# source_eagle.net
KiCad netlist of a schematic drawn in EAGLE
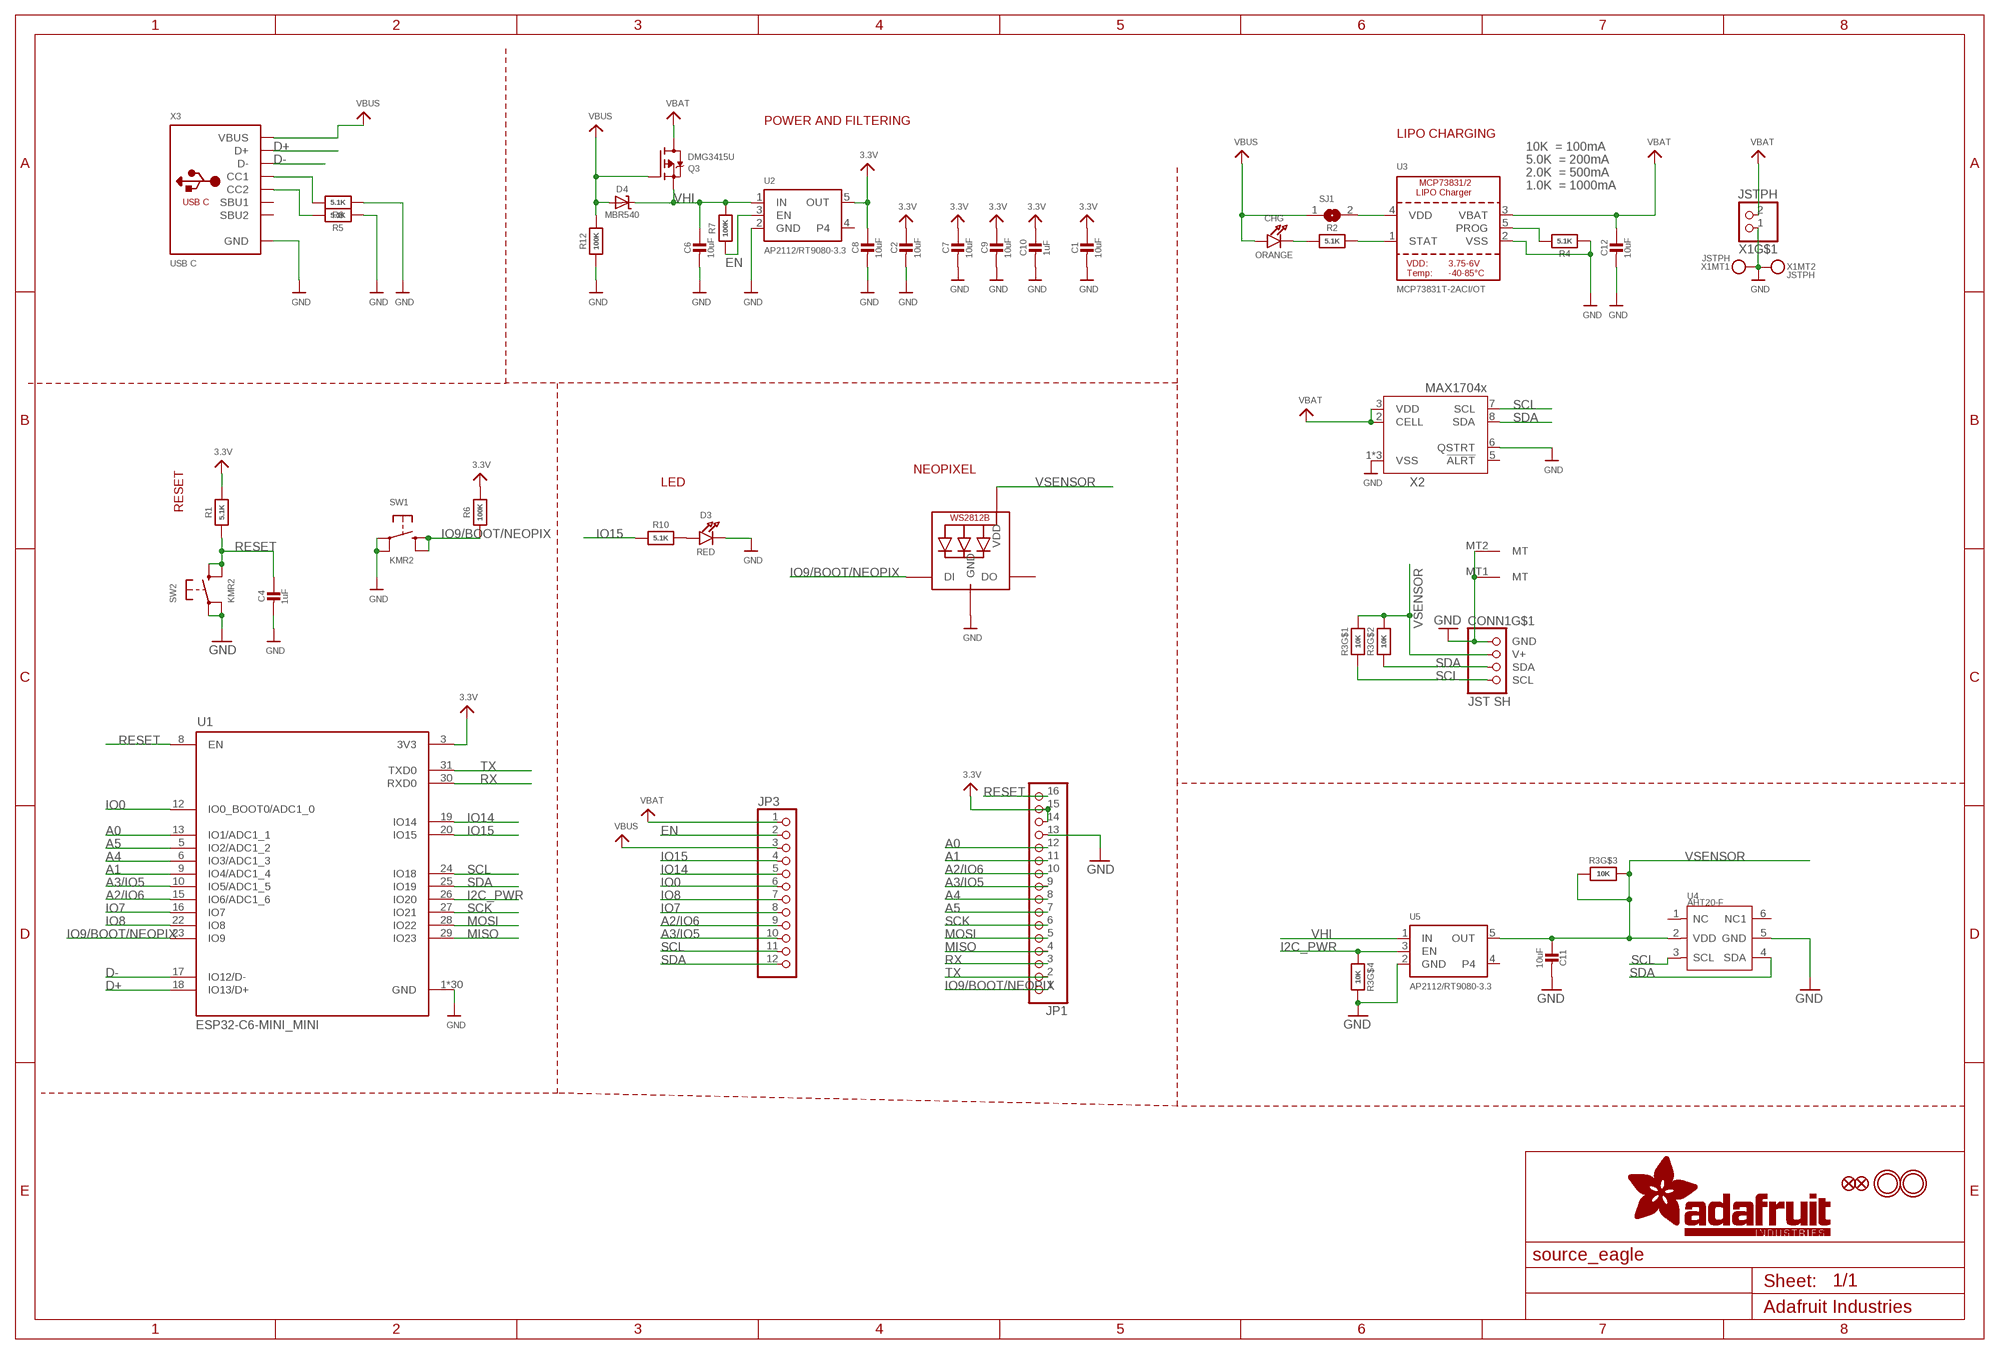
[diagram p0: schematic, sheet 1]

(export (version "E")
  (design (tool "Eeschema 10.0.6"))
  (components
    (comp (ref "C1")
      (value "10uF")
      (footprint "eagle-import:0805-NO")
      (libsource (lib "eagle-import") (part "CAP_CERAMIC0805-NOOUTLINE"))
    )
    (comp (ref "C2")
      (value "10uF")
      (footprint "eagle-import:0805-NO")
      (libsource (lib "eagle-import") (part "CAP_CERAMIC0805-NOOUTLINE"))
    )
    (comp (ref "C4")
      (value "1uF")
      (footprint "eagle-import:0603-NO")
      (libsource (lib "eagle-import") (part "CAP_CERAMIC0603_NO"))
    )
    (comp (ref "C6")
      (value "10uF")
      (footprint "eagle-import:0805-NO")
      (libsource (lib "eagle-import") (part "CAP_CERAMIC0805-NOOUTLINE"))
    )
    (comp (ref "C7")
      (value "10uF")
      (footprint "eagle-import:0805-NO")
      (libsource (lib "eagle-import") (part "CAP_CERAMIC0805-NOOUTLINE"))
    )
    (comp (ref "C8")
      (value "10uF")
      (footprint "eagle-import:0805-NO")
      (fields (field (name "REV") "B"))
      (libsource (lib "eagle-import") (part "CAP_CERAMIC0805-NOOUTLINE"))
    )
    (comp (ref "C9")
      (value "10uF")
      (footprint "eagle-import:0805-NO")
      (libsource (lib "eagle-import") (part "CAP_CERAMIC0805-NOOUTLINE"))
    )
    (comp (ref "C10")
      (value "1uF")
      (footprint "eagle-import:0603-NO")
      (libsource (lib "eagle-import") (part "CAP_CERAMIC0603_NO"))
    )
    (comp (ref "C11")
      (value "10uF")
      (footprint "eagle-import:0805-NO")
      (libsource (lib "eagle-import") (part "CAP_CERAMIC0805-NOOUTLINE"))
    )
    (comp (ref "C12")
      (value "10uF")
      (footprint "eagle-import:_0805MP")
      (libsource (lib "eagle-import") (part "CAP_CERAMIC_0805MP"))
    )
    (comp (ref "CHG")
      (value "ORANGE")
      (footprint "eagle-import:CHIPLED_0603_NOOUTLINE")
      (libsource (lib "eagle-import") (part "LED0603_NOOUTLINE"))
    )
    (comp (ref "CONN1")
      (value "JST SH")
      (footprint "eagle-import:JST_SH4_RA")
      (libsource (lib "eagle-import") (part "STEMMA_I2C_QTRA"))
    )
    (comp (ref "D3")
      (value "RED")
      (footprint "eagle-import:CHIPLED_0603_NOOUTLINE")
      (libsource (lib "eagle-import") (part "LED0603_NOOUTLINE"))
    )
    (comp (ref "D4")
      (value "MBR540")
      (footprint "eagle-import:SOD-123")
      (libsource (lib "eagle-import") (part "DIODE-SCHOTTKYSOD-123"))
    )
    (comp (ref "JP1")
      (value "HEADER-1X16ROUND")
      (footprint "eagle-import:1X16_ROUND")
      (libsource (lib "eagle-import") (part "HEADER-1X16ROUND"))
    )
    (comp (ref "JP3")
      (value "HEADER-1X12")
      (footprint "eagle-import:1X12_ROUND")
      (libsource (lib "eagle-import") (part "HEADER-1X12"))
    )
    (comp (ref "LED1")
      (value "WS2812B_3535FULL")
      (footprint "eagle-import:LED3535_FULLPADS")
      (libsource (lib "eagle-import") (part "WS2812B_3535FULL"))
    )
    (comp (ref "Q3")
      (value "DMG3415U")
      (footprint "eagle-import:SOT23-R")
      (libsource (lib "eagle-import") (part "MOSFET-P"))
    )
    (comp (ref "R1")
      (value "5.1K")
      (footprint "eagle-import:0603-NO")
      (libsource (lib "eagle-import") (part "RESISTOR_0603_NOOUT"))
    )
    (comp (ref "R2")
      (value "5.1K")
      (footprint "eagle-import:0603-NO")
      (libsource (lib "eagle-import") (part "RESISTOR_0603_NOOUT"))
    )
    (comp (ref "R3")
      (value "10K")
      (footprint "eagle-import:RESPACK_4X0603")
      (libsource (lib "eagle-import") (part "RESISTOR_4PACK"))
    )
    (comp (ref "R4")
      (value "5.1K")
      (footprint "eagle-import:0603-NO")
      (libsource (lib "eagle-import") (part "RESISTOR_0603_NOOUT"))
    )
    (comp (ref "R5")
      (value "5.1K")
      (footprint "eagle-import:0603-NO")
      (libsource (lib "eagle-import") (part "RESISTOR_0603_NOOUT"))
    )
    (comp (ref "R6")
      (value "100K")
      (footprint "eagle-import:0603-NO")
      (libsource (lib "eagle-import") (part "RESISTOR_0603_NOOUT"))
    )
    (comp (ref "R7")
      (value "100K")
      (footprint "eagle-import:0603-NO")
      (libsource (lib "eagle-import") (part "RESISTOR_0603_NOOUT"))
    )
    (comp (ref "R8")
      (value "5.1K")
      (footprint "eagle-import:0603-NO")
      (libsource (lib "eagle-import") (part "RESISTOR_0603_NOOUT"))
    )
    (comp (ref "R10")
      (value "5.1K")
      (footprint "eagle-import:0603-NO")
      (libsource (lib "eagle-import") (part "RESISTOR_0603_NOOUT"))
    )
    (comp (ref "R12")
      (value "100K")
      (footprint "eagle-import:0603-NO")
      (libsource (lib "eagle-import") (part "RESISTOR_0603_NOOUT"))
    )
    (comp (ref "SJ1")
      (value "SOLDERJUMPERCLOSED")
      (footprint "eagle-import:SOLDERJUMPER_CLOSEDWIRE")
      (libsource (lib "eagle-import") (part "SOLDERJUMPERCLOSED"))
    )
    (comp (ref "SW1")
      (value "KMR2")
      (footprint "eagle-import:BTN_RKB2_4.6X2.8")
      (libsource (lib "eagle-import") (part "SWITCH_TACT_SMT_RKB2"))
    )
    (comp (ref "SW2")
      (value "KMR2")
      (footprint "eagle-import:BTN_RKB2_4.6X2.8")
      (libsource (lib "eagle-import") (part "SWITCH_TACT_SMT_RKB2"))
    )
    (comp (ref "U$31")
      (value "MOUNTINGHOLE2.5")
      (footprint "eagle-import:MOUNTINGHOLE_2.5_PLATED")
      (libsource (lib "eagle-import") (part "MOUNTINGHOLE2.5"))
    )
    (comp (ref "U$32")
      (value "MOUNTINGHOLE2.5")
      (footprint "eagle-import:MOUNTINGHOLE_2.5_PLATED")
      (libsource (lib "eagle-import") (part "MOUNTINGHOLE2.5"))
    )
    (comp (ref "U$34")
      (value "FIDUCIAL_1MM")
      (footprint "eagle-import:FIDUCIAL_1MM")
      (libsource (lib "eagle-import") (part "FIDUCIAL_1MM"))
    )
    (comp (ref "U$35")
      (value "FIDUCIAL_1MM")
      (footprint "eagle-import:FIDUCIAL_1MM")
      (libsource (lib "eagle-import") (part "FIDUCIAL_1MM"))
    )
    (comp (ref "U1")
      (value "ESP32-C6-MINI_MINI")
      (footprint "eagle-import:ESP32-PICO-MINI")
      (libsource (lib "eagle-import") (part "ESP32-C6-MINI_MINI"))
    )
    (comp (ref "U2")
      (value "AP2112/RT9080-3.3")
      (footprint "eagle-import:SOT23-5")
      (fields (field (name "JLC_ROTATION") "0"))
      (libsource (lib "eagle-import") (part "VREG_SOT23-5"))
    )
    (comp (ref "U3")
      (value "MCP73831T-2ACI/OT")
      (footprint "eagle-import:SOT23-5")
      (fields (field (name "JLC_ROTATION") "0"))
      (libsource (lib "eagle-import") (part "MCP73831/2"))
    )
    (comp (ref "U4")
      (value "AHT20-F")
      (footprint "eagle-import:LONGAN-IC_SNR6-1.0-3X3X1MM")
      (fields (field (name "LCSC_PART") "C2757850"))
      (libsource (lib "eagle-import") (part "AHT20"))
    )
    (comp (ref "U5")
      (value "AP2112/RT9080-3.3")
      (footprint "eagle-import:SOT23-5")
      (fields (field (name "JLC_ROTATION") "0"))
      (libsource (lib "eagle-import") (part "VREG_SOT23-5"))
    )
    (comp (ref "X1")
      (value "JSTPH")
      (footprint "eagle-import:JSTPH2_BATT")
      (libsource (lib "eagle-import") (part "CON_JST_PH_2PIN_MT_BATT"))
    )
    (comp (ref "X2")
      (value "MAX17048/T")
      (footprint "eagle-import:TDFN8_2X2MM")
      (libsource (lib "eagle-import") (part "MAX17048/T"))
    )
    (comp (ref "X3")
      (value "USB C")
      (footprint "eagle-import:USB_C_CUSB31-CFM2AX-01-X")
      (libsource (lib "eagle-import") (part "USB_C"))
    )
  )
  (nets
    (net (code "1") (name "/A0") (class "Default")
      (node (ref "JP1") (pin "12") (pinfunction "12_12") (pintype "passive"))
      (node (ref "U1") (pin "13") (pinfunction "IO1/ADC1_1_13") (pintype "bidirectional"))
    )
    (net (code "2") (name "/A1") (class "Default")
      (node (ref "JP1") (pin "11") (pinfunction "11_11") (pintype "passive"))
      (node (ref "U1") (pin "9") (pinfunction "IO4/ADC1_4_9") (pintype "bidirectional"))
    )
    (net (code "3") (name "/A2{slash}IO6") (class "Default")
      (node (ref "JP1") (pin "10") (pinfunction "10_10") (pintype "passive"))
      (node (ref "JP3") (pin "9") (pinfunction "9_9") (pintype "passive"))
      (node (ref "U1") (pin "15") (pinfunction "IO6/ADC1_6_15") (pintype "bidirectional"))
    )
    (net (code "4") (name "/A3{slash}IO5") (class "Default")
      (node (ref "JP1") (pin "9") (pinfunction "9_9") (pintype "passive"))
      (node (ref "JP3") (pin "10") (pinfunction "10_10") (pintype "passive"))
      (node (ref "U1") (pin "10") (pinfunction "IO5/ADC1_5_10") (pintype "bidirectional"))
    )
    (net (code "5") (name "/A4") (class "Default")
      (node (ref "JP1") (pin "8") (pinfunction "8_8") (pintype "passive"))
      (node (ref "U1") (pin "6") (pinfunction "IO3/ADC1_3_6") (pintype "bidirectional"))
    )
    (net (code "6") (name "/A5") (class "Default")
      (node (ref "JP1") (pin "7") (pinfunction "7_7") (pintype "passive"))
      (node (ref "U1") (pin "5") (pinfunction "IO2/ADC1_2_5") (pintype "bidirectional"))
    )
    (net (code "7") (name "/D+") (class "Default")
      (node (ref "U1") (pin "18") (pinfunction "IO13/D+_18") (pintype "bidirectional"))
      (node (ref "X3") (pin "A6") (pinfunction "D+_A6") (pintype "bidirectional"))
      (node (ref "X3") (pin "B6") (pinfunction "D+_B6") (pintype "bidirectional"))
    )
    (net (code "8") (name "/D-") (class "Default")
      (node (ref "U1") (pin "17") (pinfunction "IO12/D-_17") (pintype "bidirectional"))
      (node (ref "X3") (pin "A7") (pinfunction "D-_A7") (pintype "bidirectional"))
      (node (ref "X3") (pin "B7") (pinfunction "D-_B7") (pintype "bidirectional"))
    )
    (net (code "9") (name "/EN") (class "Default")
      (node (ref "JP3") (pin "2") (pinfunction "2_2") (pintype "passive"))
      (node (ref "R7") (pin "1") (pinfunction "1_1") (pintype "passive"))
      (node (ref "U2") (pin "3") (pinfunction "EN_3") (pintype "input"))
    )
    (net (code "10") (name "/I2C_PWR") (class "Default")
      (node (ref "R3") (pin "5") (pinfunction "2_5") (pintype "passive"))
      (node (ref "U1") (pin "26") (pinfunction "IO20_26") (pintype "bidirectional"))
      (node (ref "U5") (pin "3") (pinfunction "EN_3") (pintype "input"))
    )
    (net (code "11") (name "/IO0") (class "Default")
      (node (ref "JP3") (pin "6") (pinfunction "6_6") (pintype "passive"))
      (node (ref "U1") (pin "12") (pinfunction "IO0_BOOT0/ADC1_0_12") (pintype "bidirectional"))
    )
    (net (code "12") (name "/IO7") (class "Default")
      (node (ref "JP3") (pin "8") (pinfunction "8_8") (pintype "passive"))
      (node (ref "U1") (pin "16") (pinfunction "IO7_16") (pintype "bidirectional"))
    )
    (net (code "13") (name "/IO8") (class "Default")
      (node (ref "JP3") (pin "7") (pinfunction "7_7") (pintype "passive"))
      (node (ref "U1") (pin "22") (pinfunction "IO8_22") (pintype "bidirectional"))
    )
    (net (code "14") (name "/IO9{slash}BOOT{slash}NEOPIX") (class "Default")
      (node (ref "JP1") (pin "1") (pinfunction "1_1") (pintype "passive"))
      (node (ref "LED1") (pin "1") (pinfunction "DI_1") (pintype "input"))
      (node (ref "R6") (pin "1") (pinfunction "1_1") (pintype "passive"))
      (node (ref "SW1") (pin "B") (pinfunction "S_B") (pintype "passive"))
      (node (ref "SW1") (pin "B'") (pinfunction "S1_B'") (pintype "passive"))
      (node (ref "U1") (pin "23") (pinfunction "IO9_23") (pintype "bidirectional"))
    )
    (net (code "15") (name "/IO14") (class "Default")
      (node (ref "JP3") (pin "5") (pinfunction "5_5") (pintype "passive"))
      (node (ref "U1") (pin "19") (pinfunction "IO14_19") (pintype "bidirectional"))
    )
    (net (code "16") (name "/IO15") (class "Default")
      (node (ref "JP3") (pin "4") (pinfunction "4_4") (pintype "passive"))
      (node (ref "R10") (pin "1") (pinfunction "1_1") (pintype "passive"))
      (node (ref "U1") (pin "20") (pinfunction "IO15_20") (pintype "bidirectional"))
    )
    (net (code "17") (name "/MISO") (class "Default")
      (node (ref "JP1") (pin "4") (pinfunction "4_4") (pintype "passive"))
      (node (ref "U1") (pin "29") (pinfunction "IO23_29") (pintype "bidirectional"))
    )
    (net (code "18") (name "/MOSI") (class "Default")
      (node (ref "JP1") (pin "5") (pinfunction "5_5") (pintype "passive"))
      (node (ref "U1") (pin "28") (pinfunction "IO22_28") (pintype "bidirectional"))
    )
    (net (code "19") (name "/RESET") (class "Default")
      (node (ref "C4") (pin "1") (pinfunction "1_1") (pintype "passive"))
      (node (ref "JP1") (pin "16") (pinfunction "16_16") (pintype "passive"))
      (node (ref "R1") (pin "1") (pinfunction "1_1") (pintype "passive"))
      (node (ref "SW2") (pin "B") (pinfunction "S_B") (pintype "passive"))
      (node (ref "SW2") (pin "B'") (pinfunction "S1_B'") (pintype "passive"))
      (node (ref "U1") (pin "8") (pinfunction "EN_8") (pintype "input"))
    )
    (net (code "20") (name "/RX") (class "Default")
      (node (ref "JP1") (pin "3") (pinfunction "3_3") (pintype "passive"))
      (node (ref "U1") (pin "30") (pinfunction "RXD0_30") (pintype "bidirectional"))
    )
    (net (code "21") (name "/SCK") (class "Default")
      (node (ref "JP1") (pin "6") (pinfunction "6_6") (pintype "passive"))
      (node (ref "U1") (pin "27") (pinfunction "IO21_27") (pintype "bidirectional"))
    )
    (net (code "22") (name "/SCL") (class "Default")
      (node (ref "CONN1") (pin "4") (pinfunction "SCL_4") (pintype "passive"))
      (node (ref "JP3") (pin "11") (pinfunction "11_11") (pintype "passive"))
      (node (ref "R3") (pin "1") (pinfunction "1_1") (pintype "passive"))
      (node (ref "U1") (pin "24") (pinfunction "IO18_24") (pintype "bidirectional"))
      (node (ref "U4") (pin "3") (pinfunction "SCL_3") (pintype "bidirectional"))
      (node (ref "X2") (pin "7") (pinfunction "SCL_7") (pintype "bidirectional"))
    )
    (net (code "23") (name "/SDA") (class "Default")
      (node (ref "CONN1") (pin "3") (pinfunction "SDA_3") (pintype "passive"))
      (node (ref "JP3") (pin "12") (pinfunction "12_12") (pintype "passive"))
      (node (ref "R3") (pin "2") (pinfunction "1_2") (pintype "passive"))
      (node (ref "U1") (pin "25") (pinfunction "IO19_25") (pintype "bidirectional"))
      (node (ref "U4") (pin "4") (pinfunction "SDA_4") (pintype "bidirectional"))
      (node (ref "X2") (pin "8") (pinfunction "SDA_8") (pintype "bidirectional"))
    )
    (net (code "24") (name "/TX") (class "Default")
      (node (ref "JP1") (pin "2") (pinfunction "2_2") (pintype "passive"))
      (node (ref "U1") (pin "31") (pinfunction "TXD0_31") (pintype "bidirectional"))
    )
    (net (code "25") (name "/VHI") (class "Default")
      (node (ref "C6") (pin "1") (pinfunction "1_1") (pintype "passive"))
      (node (ref "D4") (pin "C") (pinfunction "C_C") (pintype "passive"))
      (node (ref "Q3") (pin "2") (pinfunction "S_2") (pintype "passive"))
      (node (ref "R7") (pin "2") (pinfunction "2_2") (pintype "passive"))
      (node (ref "U2") (pin "1") (pinfunction "IN_1") (pintype "power_in"))
      (node (ref "U5") (pin "1") (pinfunction "IN_1") (pintype "power_in"))
    )
    (net (code "26") (name "/VSENSOR") (class "Default")
      (node (ref "C11") (pin "1") (pinfunction "1_1") (pintype "passive"))
      (node (ref "CONN1") (pin "2") (pinfunction "V+_2") (pintype "passive"))
      (node (ref "LED1") (pin "2") (pinfunction "VDD_2") (pintype "power_in"))
      (node (ref "R3") (pin "3") (pinfunction "1_3") (pintype "passive"))
      (node (ref "R3") (pin "6") (pinfunction "2_6") (pintype "passive"))
      (node (ref "R3") (pin "7") (pinfunction "2_7") (pintype "passive"))
      (node (ref "R3") (pin "8") (pinfunction "2_8") (pintype "passive"))
      (node (ref "U4") (pin "2") (pinfunction "VDD_2") (pintype "bidirectional"))
      (node (ref "U5") (pin "5") (pinfunction "OUT_5") (pintype "power_in"))
    )
    (net (code "27") (name "3.3V") (class "Default")
      (node (ref "C1") (pin "1") (pinfunction "1_1") (pintype "passive"))
      (node (ref "C10") (pin "1") (pinfunction "1_1") (pintype "passive"))
      (node (ref "C2") (pin "1") (pinfunction "1_1") (pintype "passive"))
      (node (ref "C7") (pin "1") (pinfunction "1_1") (pintype "passive"))
      (node (ref "C8") (pin "1") (pinfunction "1_1") (pintype "passive"))
      (node (ref "C9") (pin "1") (pinfunction "1_1") (pintype "passive"))
      (node (ref "JP1") (pin "14") (pinfunction "14_14") (pintype "passive"))
      (node (ref "JP1") (pin "15") (pinfunction "15_15") (pintype "passive"))
      (node (ref "R1") (pin "2") (pinfunction "2_2") (pintype "passive"))
      (node (ref "R6") (pin "2") (pinfunction "2_2") (pintype "passive"))
      (node (ref "U1") (pin "3") (pinfunction "3V3_3") (pintype "power_in"))
      (node (ref "U2") (pin "5") (pinfunction "OUT_5") (pintype "power_in"))
    )
    (net (code "28") (name "GND") (class "Default")
      (node (ref "C1") (pin "2") (pinfunction "2_2") (pintype "passive"))
      (node (ref "C10") (pin "2") (pinfunction "2_2") (pintype "passive"))
      (node (ref "C11") (pin "2") (pinfunction "2_2") (pintype "passive"))
      (node (ref "C12") (pin "2") (pinfunction "2_2") (pintype "passive"))
      (node (ref "C2") (pin "2") (pinfunction "2_2") (pintype "passive"))
      (node (ref "C4") (pin "2") (pinfunction "2_2") (pintype "passive"))
      (node (ref "C6") (pin "2") (pinfunction "2_2") (pintype "passive"))
      (node (ref "C7") (pin "2") (pinfunction "2_2") (pintype "passive"))
      (node (ref "C8") (pin "2") (pinfunction "2_2") (pintype "passive"))
      (node (ref "C9") (pin "2") (pinfunction "2_2") (pintype "passive"))
      (node (ref "CONN1") (pin "1") (pinfunction "GND_1") (pintype "passive"))
      (node (ref "CONN1") (pin "MT1") (pinfunction "MT_MT1") (pintype "bidirectional"))
      (node (ref "CONN1") (pin "MT2") (pinfunction "MT_MT2") (pintype "bidirectional"))
      (node (ref "D3") (pin "C") (pinfunction "C_C") (pintype "passive"))
      (node (ref "JP1") (pin "13") (pinfunction "13_13") (pintype "passive"))
      (node (ref "LED1") (pin "4") (pinfunction "GND_4") (pintype "power_in"))
      (node (ref "R12") (pin "1") (pinfunction "1_1") (pintype "passive"))
      (node (ref "R3") (pin "4") (pinfunction "1_4") (pintype "passive"))
      (node (ref "R4") (pin "1") (pinfunction "1_1") (pintype "passive"))
      (node (ref "R5") (pin "1") (pinfunction "1_1") (pintype "passive"))
      (node (ref "R8") (pin "1") (pinfunction "1_1") (pintype "passive"))
      (node (ref "SW1") (pin "A") (pinfunction "P_A") (pintype "passive"))
      (node (ref "SW1") (pin "A'") (pinfunction "P1_A'") (pintype "passive"))
      (node (ref "SW2") (pin "A") (pinfunction "P_A") (pintype "passive"))
      (node (ref "SW2") (pin "A'") (pinfunction "P1_A'") (pintype "passive"))
      (node (ref "U1") (pin "1") (pinfunction "GND_1") (pintype "power_in"))
      (node (ref "U1") (pin "11") (pinfunction "GND_11") (pintype "power_in"))
      (node (ref "U1") (pin "14") (pinfunction "GND_14") (pintype "power_in"))
      (node (ref "U1") (pin "2") (pinfunction "GND_2") (pintype "power_in"))
      (node (ref "U1") (pin "36") (pinfunction "GND_36") (pintype "power_in"))
      (node (ref "U1") (pin "37") (pinfunction "GND_37") (pintype "power_in"))
      (node (ref "U1") (pin "38") (pinfunction "GND_38") (pintype "power_in"))
      (node (ref "U1") (pin "39") (pinfunction "GND_39") (pintype "power_in"))
      (node (ref "U1") (pin "40") (pinfunction "GND_40") (pintype "power_in"))
      (node (ref "U1") (pin "41") (pinfunction "GND_41") (pintype "power_in"))
      (node (ref "U1") (pin "42") (pinfunction "GND_42") (pintype "power_in"))
      (node (ref "U1") (pin "43") (pinfunction "GND_43") (pintype "power_in"))
      (node (ref "U1") (pin "44") (pinfunction "GND_44") (pintype "power_in"))
      (node (ref "U1") (pin "45") (pinfunction "GND_45") (pintype "power_in"))
      (node (ref "U1") (pin "46") (pinfunction "GND_46") (pintype "power_in"))
      (node (ref "U1") (pin "47") (pinfunction "GND_47") (pintype "power_in"))
      (node (ref "U1") (pin "48") (pinfunction "GND_48") (pintype "power_in"))
      (node (ref "U1") (pin "49") (pinfunction "GND_49") (pintype "power_in"))
      (node (ref "U1") (pin "50") (pinfunction "GND_50") (pintype "power_in"))
      (node (ref "U1") (pin "51") (pinfunction "GND_51") (pintype "power_in"))
      (node (ref "U1") (pin "52") (pinfunction "GND_52") (pintype "power_in"))
      (node (ref "U1") (pin "53") (pinfunction "GND_53") (pintype "power_in"))
      (node (ref "U1") (pin "54") (pinfunction "GND_54") (pintype "power_in"))
      (node (ref "U1") (pin "55") (pinfunction "GND_55") (pintype "power_in"))
      (node (ref "U1") (pin "56") (pinfunction "GND_56") (pintype "power_in"))
      (node (ref "U1") (pin "57") (pinfunction "GND_57") (pintype "power_in"))
      (node (ref "U1") (pin "58") (pinfunction "GND_58") (pintype "power_in"))
      (node (ref "U1") (pin "59") (pinfunction "GND_59") (pintype "power_in"))
      (node (ref "U1") (pin "60") (pinfunction "GND_60") (pintype "power_in"))
      (node (ref "U1") (pin "61") (pinfunction "GND_61") (pintype "power_in"))
      (node (ref "U2") (pin "2") (pinfunction "GND_2") (pintype "power_in"))
      (node (ref "U3") (pin "2") (pinfunction "VSS_2") (pintype "power_in"))
      (node (ref "U4") (pin "5") (pinfunction "GND_5") (pintype "bidirectional"))
      (node (ref "U5") (pin "2") (pinfunction "GND_2") (pintype "power_in"))
      (node (ref "X1") (pin "1") (pinfunction "1_1") (pintype "passive"))
      (node (ref "X1") (pin "NC1") (pinfunction "P$1_NC1") (pintype "bidirectional"))
      (node (ref "X1") (pin "NC2") (pinfunction "P$1_NC2") (pintype "bidirectional"))
      (node (ref "X2") (pin "1") (pinfunction "VSS_1") (pintype "power_in"))
      (node (ref "X2") (pin "4") (pinfunction "VSS_4") (pintype "power_in"))
      (node (ref "X2") (pin "6") (pinfunction "QSTRT_6") (pintype "input"))
      (node (ref "X2") (pin "THERMAL") (pinfunction "VSS_THERMAL") (pintype "power_in"))
      (node (ref "X3") (pin "A1B12") (pinfunction "GND_A1B12") (pintype "power_in"))
      (node (ref "X3") (pin "B1A12") (pinfunction "GND_B1A12") (pintype "power_in"))
    )
    (net (code "29") (name "Net-(CHG-PadC)") (class "Default")
      (node (ref "CHG") (pin "C") (pinfunction "C_C") (pintype "passive"))
      (node (ref "R2") (pin "1") (pinfunction "1_1") (pintype "passive"))
    )
    (net (code "30") (name "Net-(D3-PadA)") (class "Default")
      (node (ref "D3") (pin "A") (pinfunction "A_A") (pintype "passive"))
      (node (ref "R10") (pin "2") (pinfunction "2_2") (pintype "passive"))
    )
    (net (code "31") (name "Net-(U3-PROG)") (class "Default")
      (node (ref "R4") (pin "2") (pinfunction "2_2") (pintype "passive"))
      (node (ref "U3") (pin "5") (pinfunction "PROG_5") (pintype "input"))
    )
    (net (code "32") (name "Net-(U3-STAT)") (class "Default")
      (node (ref "R2") (pin "2") (pinfunction "2_2") (pintype "passive"))
      (node (ref "U3") (pin "1") (pinfunction "STAT_1") (pintype "output"))
    )
    (net (code "33") (name "Net-(U3-VDD)") (class "Default")
      (node (ref "SJ1") (pin "2") (pinfunction "2_2") (pintype "passive"))
      (node (ref "U3") (pin "4") (pinfunction "VDD_4") (pintype "power_in"))
    )
    (net (code "34") (name "Net-(X3-CC1)") (class "Default")
      (node (ref "R8") (pin "2") (pinfunction "2_2") (pintype "passive"))
      (node (ref "X3") (pin "A5") (pinfunction "CC1_A5") (pintype "bidirectional"))
    )
    (net (code "35") (name "Net-(X3-CC2)") (class "Default")
      (node (ref "R5") (pin "2") (pinfunction "2_2") (pintype "passive"))
      (node (ref "X3") (pin "B5") (pinfunction "CC2_B5") (pintype "bidirectional"))
    )
    (net (code "36") (name "VBAT") (class "Default")
      (node (ref "C12") (pin "1") (pinfunction "1_1") (pintype "passive"))
      (node (ref "JP3") (pin "1") (pinfunction "1_1") (pintype "passive"))
      (node (ref "Q3") (pin "3") (pinfunction "D_3") (pintype "passive"))
      (node (ref "U3") (pin "3") (pinfunction "VBAT_3") (pintype "power_in"))
      (node (ref "X1") (pin "2") (pinfunction "2_2") (pintype "passive"))
      (node (ref "X2") (pin "2") (pinfunction "CELL_2") (pintype "power_in"))
      (node (ref "X2") (pin "3") (pinfunction "VDD_3") (pintype "power_in"))
    )
    (net (code "37") (name "VBUS") (class "Default")
      (node (ref "CHG") (pin "A") (pinfunction "A_A") (pintype "passive"))
      (node (ref "D4") (pin "A") (pinfunction "A_A") (pintype "passive"))
      (node (ref "JP3") (pin "3") (pinfunction "3_3") (pintype "passive"))
      (node (ref "Q3") (pin "1") (pinfunction "G_1") (pintype "passive"))
      (node (ref "R12") (pin "2") (pinfunction "2_2") (pintype "passive"))
      (node (ref "SJ1") (pin "1") (pinfunction "1_1") (pintype "passive"))
      (node (ref "X3") (pin "A4B9") (pinfunction "VBUS_A4B9") (pintype "power_in"))
      (node (ref "X3") (pin "B4A9") (pinfunction "VBUS_B4A9") (pintype "power_in"))
    )
    (net (code "38") (name "unconnected-(LED1-DO-Pad3)") (class "Default")
      (node (ref "LED1") (pin "3") (pinfunction "DO_3") (pintype "output"))
    )
    (net (code "39") (name "unconnected-(U2-P4-Pad4)") (class "Default")
      (node (ref "U2") (pin "4") (pinfunction "P4_4") (pintype "bidirectional"))
    )
    (net (code "40") (name "unconnected-(U4-NC-Pad1)") (class "Default")
      (node (ref "U4") (pin "1") (pinfunction "NC_1") (pintype "bidirectional"))
    )
    (net (code "41") (name "unconnected-(U4-NC1-Pad6)") (class "Default")
      (node (ref "U4") (pin "6") (pinfunction "NC1_6") (pintype "bidirectional"))
    )
    (net (code "42") (name "unconnected-(U5-P4-Pad4)") (class "Default")
      (node (ref "U5") (pin "4") (pinfunction "P4_4") (pintype "bidirectional"))
    )
    (net (code "43") (name "unconnected-(X2-~{ALRT}-Pad5)") (class "Default")
      (node (ref "X2") (pin "5") (pinfunction "~{ALRT}_5") (pintype "output"))
    )
    (net (code "44") (name "unconnected-(X3-SBU1-PadA8)") (class "Default")
      (node (ref "X3") (pin "A8") (pinfunction "SBU1_A8") (pintype "bidirectional"))
    )
    (net (code "45") (name "unconnected-(X3-SBU2-PadB8)") (class "Default")
      (node (ref "X3") (pin "B8") (pinfunction "SBU2_B8") (pintype "bidirectional"))
    )
  )
)
